# D32_Pro_Benchtop_Test_Board.net
KiCad netlist of a schematic drawn in EAGLE
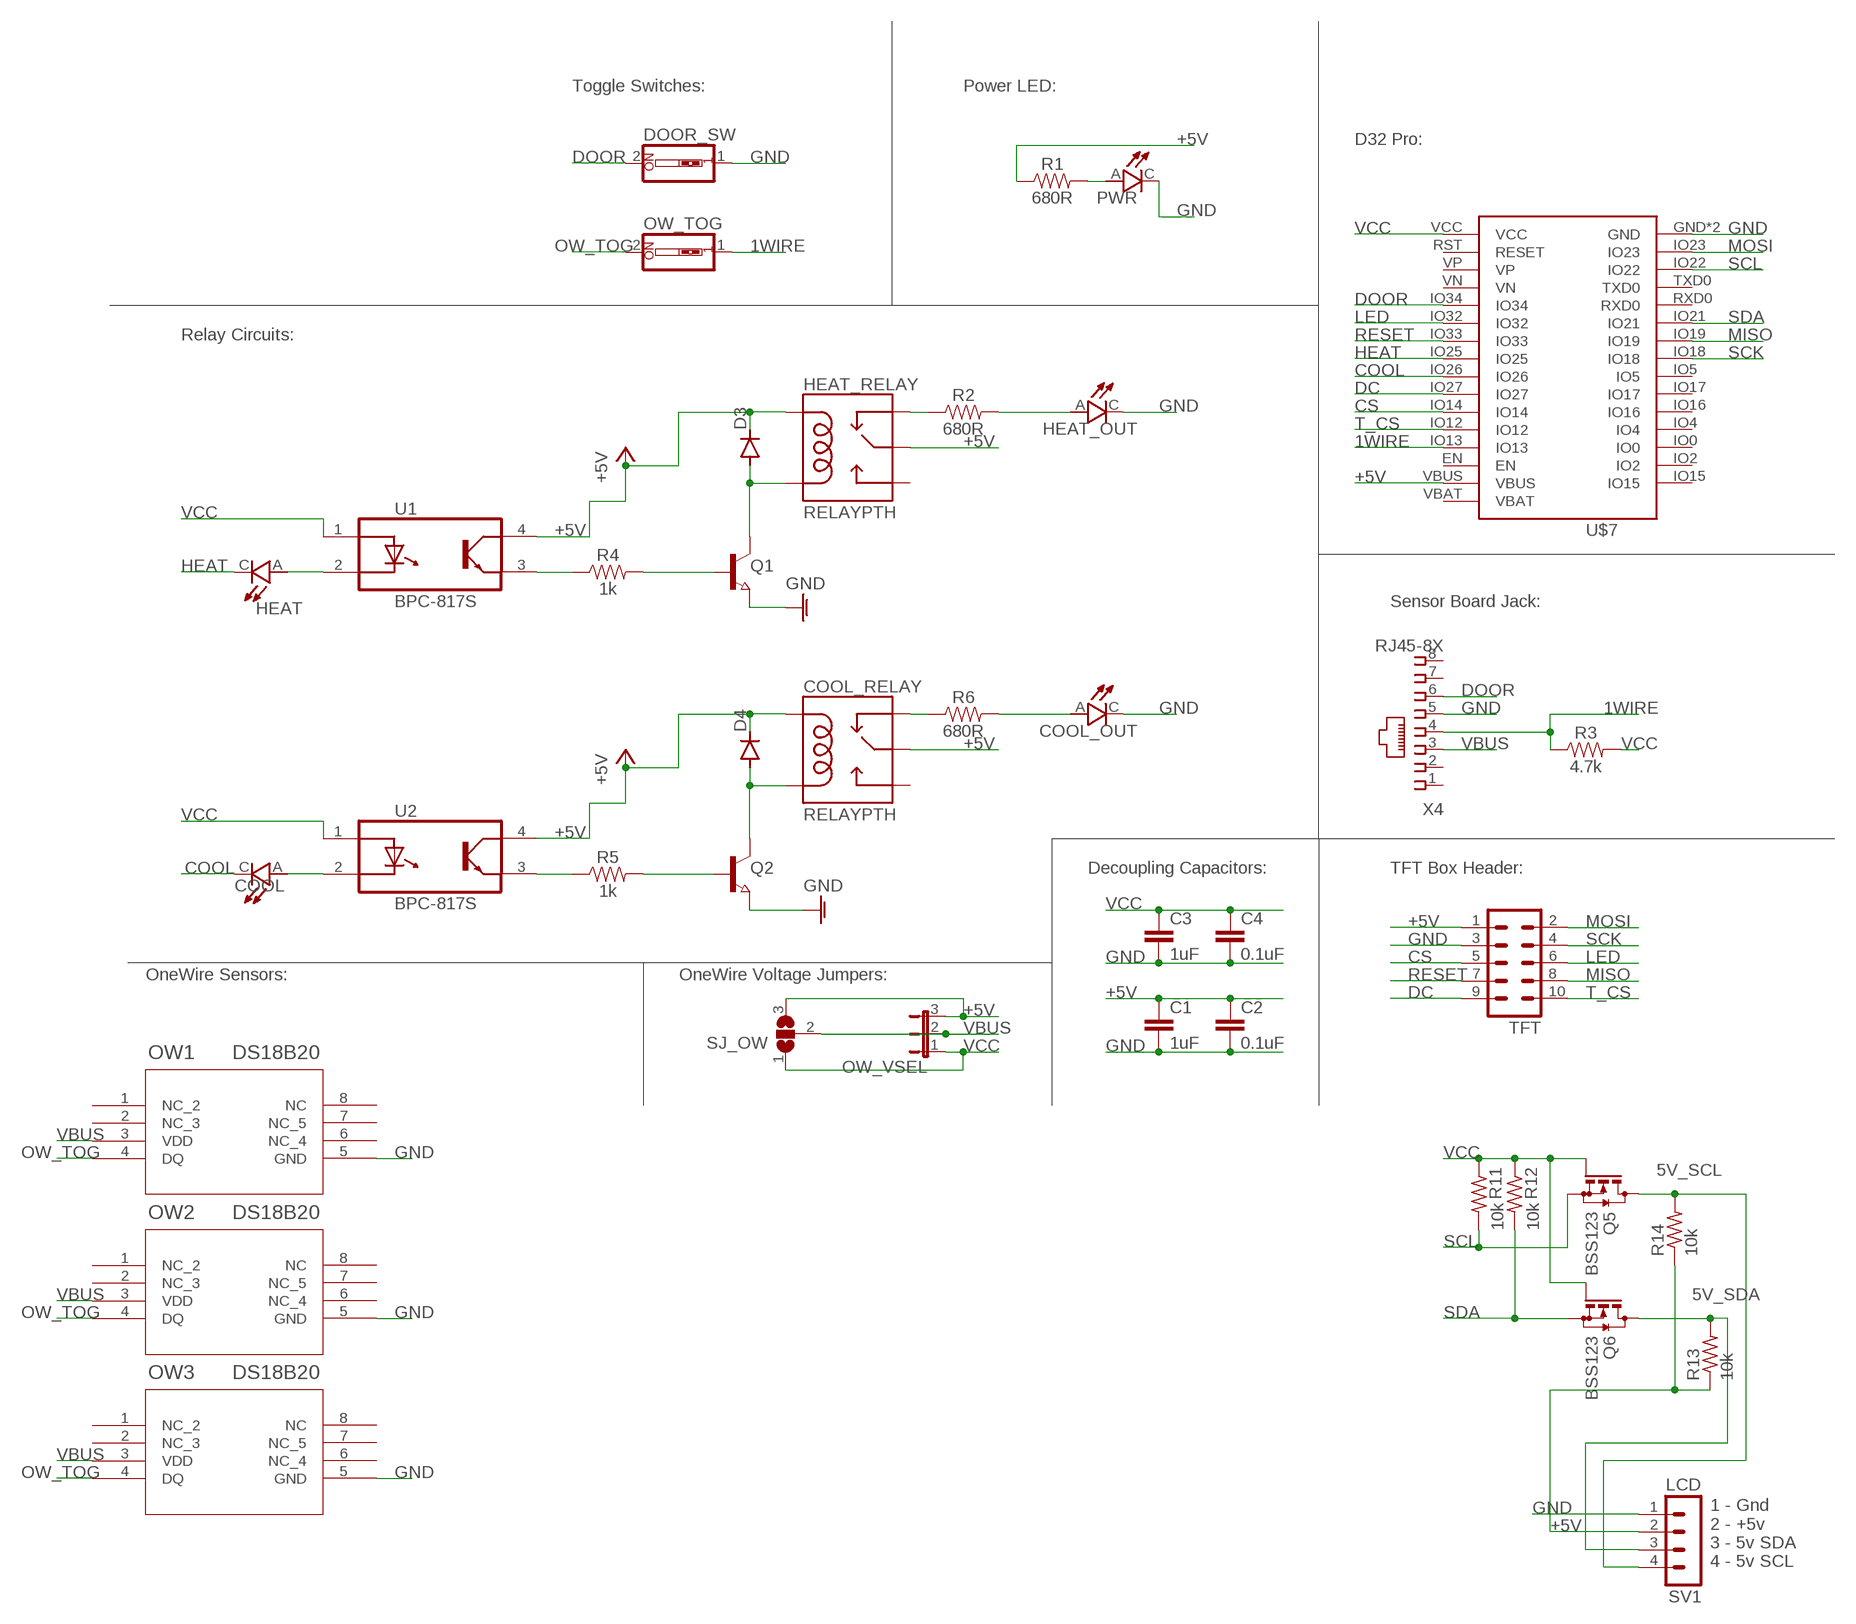
[diagram p0: schematic, sheet 1]

(export (version "E")
  (design (tool "Eeschema 10.0.6"))
  (components
    (comp (ref "C1")
      (value "1uF")
      (footprint "eagle-import:SMD-0805")
      (fields (field (name "LCSC_PART") "C28323"))
      (libsource (lib "eagle-import") (part "CAP_SMD0805"))
    )
    (comp (ref "C2")
      (value "0.1uF")
      (footprint "eagle-import:SMD-0805")
      (fields (field (name "LCSC_PART") "C49678"))
      (libsource (lib "eagle-import") (part "CAP_SMD0805"))
    )
    (comp (ref "C3")
      (value "1uF")
      (footprint "eagle-import:SMD-0805")
      (fields (field (name "LCSC_PART") "C28323"))
      (libsource (lib "eagle-import") (part "CAP_SMD0805"))
    )
    (comp (ref "C4")
      (value "0.1uF")
      (footprint "eagle-import:SMD-0805")
      (fields (field (name "LCSC_PART") "C49678"))
      (libsource (lib "eagle-import") (part "CAP_SMD0805"))
    )
    (comp (ref "COOL")
      (value "LED_0603LED_SMD_0603")
      (footprint "eagle-import:LED_SMD_0603")
      (fields (field (name "LCSC_PART") "C2286") (field (name "LCSC_PART_1") "C2286"))
      (libsource (lib "eagle-import") (part "LED_0603LED_SMD_0603"))
    )
    (comp (ref "COOL_OUT")
      (value "LED_0603LED_SMD_0603")
      (footprint "eagle-import:LED_SMD_0603")
      (fields (field (name "LCSC_PART") "C2286"))
      (libsource (lib "eagle-import") (part "LED_0603LED_SMD_0603"))
    )
    (comp (ref "COOL_RELAY")
      (value "RELAYPTH")
      (footprint "eagle-import:SRD-05VDC-SL-C")
      (fields (field (name "LCSC_PART") "C35449"))
      (libsource (lib "eagle-import") (part "RELAYPTH"))
    )
    (comp (ref "D3")
      (value "DIODE-DO214AC")
      (footprint "eagle-import:DO214AC")
      (fields (field (name "LCSC_PART") "C95872"))
      (libsource (lib "eagle-import") (part "DIODE-DO214AC"))
    )
    (comp (ref "D4")
      (value "DIODE-DO214AC")
      (footprint "eagle-import:DO214AC")
      (fields (field (name "LCSC_PART") "C95872"))
      (libsource (lib "eagle-import") (part "DIODE-DO214AC"))
    )
    (comp (ref "DOOR_SW")
      (value "SW_DIP-1")
      (footprint "eagle-import:EDG-01")
      (fields (field (name "LCSC_PART") "C126888"))
      (libsource (lib "eagle-import") (part "SW_DIP-1"))
    )
    (comp (ref "HEAT")
      (value "LED_0603LED_SMD_0603")
      (footprint "eagle-import:LED_SMD_0603")
      (fields (field (name "LCSC_PART") "C2286") (field (name "LCSC_PART_1") "C2286"))
      (libsource (lib "eagle-import") (part "LED_0603LED_SMD_0603"))
    )
    (comp (ref "HEAT_OUT")
      (value "LED_0603LED_SMD_0603")
      (footprint "eagle-import:LED_SMD_0603")
      (fields (field (name "LCSC_PART") "C2286"))
      (libsource (lib "eagle-import") (part "LED_0603LED_SMD_0603"))
    )
    (comp (ref "HEAT_RELAY")
      (value "RELAYPTH")
      (footprint "eagle-import:SRD-05VDC-SL-C")
      (fields (field (name "LCSC_PART") "C35449"))
      (libsource (lib "eagle-import") (part "RELAYPTH"))
    )
    (comp (ref "OW1")
      (value "DS18B20")
      (footprint "eagle-import:21-0041B_8_MXM")
      (fields
        (field (name "LCSC_PART") "C695837")
        (field (name "MANUFACTURER_PART_NUMBER") "DS18B20Z+T&R")
        (field (name "COPYRIGHT") "Copyright (C) 2024 Ultra Librarian. All rights reserved.")
      )
      (libsource (lib "eagle-import") (part "DS18B20Z+T&R"))
    )
    (comp (ref "OW2")
      (value "DS18B20")
      (footprint "eagle-import:21-0041B_8_MXM")
      (fields
        (field (name "LCSC_PART") "C695837")
        (field (name "MANUFACTURER_PART_NUMBER") "DS18B20Z+T&R")
        (field (name "COPYRIGHT") "Copyright (C) 2024 Ultra Librarian. All rights reserved.")
      )
      (libsource (lib "eagle-import") (part "DS18B20Z+T&R"))
    )
    (comp (ref "OW3")
      (value "DS18B20")
      (footprint "eagle-import:21-0041B_8_MXM")
      (fields
        (field (name "LCSC_PART") "C695837")
        (field (name "MANUFACTURER_PART_NUMBER") "DS18B20Z+T&R")
        (field (name "COPYRIGHT") "Copyright (C) 2024 Ultra Librarian. All rights reserved.")
      )
      (libsource (lib "eagle-import") (part "DS18B20Z+T&R"))
    )
    (comp (ref "OW_TOG")
      (value "SW_DIP-1")
      (footprint "eagle-import:EDG-01")
      (fields (field (name "LCSC_PART") "C126888"))
      (libsource (lib "eagle-import") (part "SW_DIP-1"))
    )
    (comp (ref "OW_VSEL")
      (value "JP2ENOLABEL")
      (footprint "eagle-import:JP2-NOLABEL")
      (fields (field (name "LCSC_PART") "C2937625"))
      (libsource (lib "eagle-import") (part "JP2ENOLABEL"))
    )
    (comp (ref "PWR")
      (value "LED_0603LED_SMD_0603")
      (footprint "eagle-import:LED_SMD_0603")
      (fields (field (name "LCSC_PART") "C2286") (field (name "LCSC_PART_1") "C2286"))
      (libsource (lib "eagle-import") (part "LED_0603LED_SMD_0603"))
    )
    (comp (ref "Q1")
      (value "NPN-TRANSISTOR_SOT23")
      (footprint "eagle-import:SOT23")
      (fields (field (name "LCSC_PART") "C20526"))
      (libsource (lib "eagle-import") (part "NPN-TRANSISTOR_SOT23"))
    )
    (comp (ref "Q2")
      (value "NPN-TRANSISTOR_SOT23")
      (footprint "eagle-import:SOT23")
      (fields (field (name "LCSC_PART") "C20526"))
      (libsource (lib "eagle-import") (part "NPN-TRANSISTOR_SOT23"))
    )
    (comp (ref "Q5")
      (value "BSS123")
      (footprint "eagle-import:SOT23")
      (fields (field (name "LCSC_PART") "C79015"))
      (libsource (lib "eagle-import") (part "BSS123"))
    )
    (comp (ref "Q6")
      (value "BSS123")
      (footprint "eagle-import:SOT23")
      (fields (field (name "LCSC_PART") "C79015"))
      (libsource (lib "eagle-import") (part "BSS123"))
    )
    (comp (ref "R1")
      (value "680R")
      (footprint "eagle-import:SMD-0805")
      (fields (field (name "LCSC_PART") "C17798"))
      (libsource (lib "eagle-import") (part "RES_SMD0805"))
    )
    (comp (ref "R2")
      (value "680R")
      (footprint "eagle-import:SMD-0805")
      (fields (field (name "LCSC_PART") "C17798"))
      (libsource (lib "eagle-import") (part "RES_SMD0805"))
    )
    (comp (ref "R3")
      (value "4.7k")
      (footprint "eagle-import:SMD-0805")
      (fields (field (name "LCSC_PART") "C17673"))
      (libsource (lib "eagle-import") (part "RES_SMD0805"))
    )
    (comp (ref "R4")
      (value "1k")
      (footprint "eagle-import:SMD-0805")
      (fields (field (name "LCSC_PART") "C17513"))
      (libsource (lib "eagle-import") (part "RES_SMD0805"))
    )
    (comp (ref "R5")
      (value "1k")
      (footprint "eagle-import:SMD-0805")
      (fields (field (name "LCSC_PART") "C17513"))
      (libsource (lib "eagle-import") (part "RES_SMD0805"))
    )
    (comp (ref "R6")
      (value "680R")
      (footprint "eagle-import:SMD-0805")
      (fields (field (name "LCSC_PART") "C17798"))
      (libsource (lib "eagle-import") (part "RES_SMD0805"))
    )
    (comp (ref "R11")
      (value "10k")
      (footprint "eagle-import:R0805")
      (fields (field (name "LCSC_PART") "C17902"))
      (libsource (lib "eagle-import") (part "R-US_R0805"))
    )
    (comp (ref "R12")
      (value "10k")
      (footprint "eagle-import:R0805")
      (fields (field (name "LCSC_PART") "C17902"))
      (libsource (lib "eagle-import") (part "R-US_R0805"))
    )
    (comp (ref "R13")
      (value "10k")
      (footprint "eagle-import:R0805")
      (fields (field (name "LCSC_PART") "C17902"))
      (libsource (lib "eagle-import") (part "R-US_R0805"))
    )
    (comp (ref "R14")
      (value "10k")
      (footprint "eagle-import:R0805")
      (fields (field (name "LCSC_PART") "C17902"))
      (libsource (lib "eagle-import") (part "R-US_R0805"))
    )
    (comp (ref "SJ_OW")
      (value "SJ2W")
      (footprint "eagle-import:SJ_2")
      (libsource (lib "eagle-import") (part "SJ2W"))
    )
    (comp (ref "SV1")
      (value "LCD")
      (footprint "eagle-import:HDR-4_VERT")
      (fields (field (name "LCSC_PART") "C2691448"))
      (libsource (lib "eagle-import") (part "HDR-4"))
    )
    (comp (ref "TFT")
      (value "MA05-2")
      (footprint "eagle-import:MA05-2")
      (libsource (lib "eagle-import") (part "MA05-2"))
    )
    (comp (ref "U$7")
      (value "WEMOS-D32D32_PRO_NO-KEEPOUT")
      (footprint "eagle-import:D32_PRO_NO-KEEPOUT")
      (fields (field (name "LCSC_PART") "C18078137"))
      (libsource (lib "eagle-import") (part "WEMOS-D32D32_PRO_NO-KEEPOUT"))
    )
    (comp (ref "U1")
      (value "BPC-817S")
      (footprint "eagle-import:SOIC127P700X210-4N")
      (fields (field (name "LCSC_PART") "C106900"))
      (libsource (lib "eagle-import") (part "BPC-817S"))
    )
    (comp (ref "U2")
      (value "BPC-817S")
      (footprint "eagle-import:SOIC127P700X210-4N")
      (fields (field (name "LCSC_PART") "C106900"))
      (libsource (lib "eagle-import") (part "BPC-817S"))
    )
    (comp (ref "X4")
      (value "RJ45-8X")
      (footprint "eagle-import:RJ45-NO-SHIELD")
      (fields
        (field (name "LCSC_PART") "C3000197")
        (field (name "JLC_Y") "7.55")
        (field (name "LCSC_PART_1") "C3000197")
      )
      (libsource (lib "eagle-import") (part "RJ45-8X"))
    )
  )
  (nets
    (net (code "1") (name "+5V") (class "Default")
      (node (ref "C1") (pin "1") (pinfunction "1_1") (pintype "passive"))
      (node (ref "C2") (pin "1") (pinfunction "1_1") (pintype "passive"))
      (node (ref "COOL_RELAY") (pin "COIL1") (pinfunction "COIL1_COIL1") (pintype "bidirectional"))
      (node (ref "COOL_RELAY") (pin "SWCOMMON") (pinfunction "SWCOMMON_SWCOMMON") (pintype "bidirectional"))
      (node (ref "D3") (pin "C") (pinfunction "C_C") (pintype "passive"))
      (node (ref "D4") (pin "C") (pinfunction "C_C") (pintype "passive"))
      (node (ref "HEAT_RELAY") (pin "COIL1") (pinfunction "COIL1_COIL1") (pintype "bidirectional"))
      (node (ref "HEAT_RELAY") (pin "SWCOMMON") (pinfunction "SWCOMMON_SWCOMMON") (pintype "bidirectional"))
      (node (ref "OW_VSEL") (pin "3") (pinfunction "3_3") (pintype "passive"))
      (node (ref "R1") (pin "1") (pinfunction "1_1") (pintype "passive"))
      (node (ref "R13") (pin "1") (pinfunction "1_1") (pintype "passive"))
      (node (ref "R14") (pin "1") (pinfunction "1_1") (pintype "passive"))
      (node (ref "SJ_OW") (pin "3") (pinfunction "3_3") (pintype "passive"))
      (node (ref "SV1") (pin "2") (pinfunction "2_2") (pintype "passive"))
      (node (ref "TFT") (pin "1") (pinfunction "1_1") (pintype "passive"))
      (node (ref "U$7") (pin "VBUS") (pinfunction "VBUS_VBUS") (pintype "bidirectional"))
      (node (ref "U1") (pin "4") (pinfunction "CO_4") (pintype "passive"))
      (node (ref "U2") (pin "4") (pinfunction "CO_4") (pintype "passive"))
    )
    (net (code "2") (name "/1WIRE") (class "Default")
      (node (ref "OW_TOG") (pin "1") (pinfunction "1_1") (pintype "passive"))
      (node (ref "R3") (pin "1") (pinfunction "1_1") (pintype "passive"))
      (node (ref "U$7") (pin "IO13") (pinfunction "IO13_IO13") (pintype "bidirectional"))
      (node (ref "X4") (pin "4") (pinfunction "4_4") (pintype "passive"))
    )
    (net (code "3") (name "/5V_SCL") (class "Default")
      (node (ref "Q5") (pin "3") (pinfunction "D_3") (pintype "passive"))
      (node (ref "R14") (pin "2") (pinfunction "2_2") (pintype "passive"))
      (node (ref "SV1") (pin "4") (pinfunction "4_4") (pintype "passive"))
    )
    (net (code "4") (name "/5V_SDA") (class "Default")
      (node (ref "Q6") (pin "3") (pinfunction "D_3") (pintype "passive"))
      (node (ref "R13") (pin "2") (pinfunction "2_2") (pintype "passive"))
      (node (ref "SV1") (pin "3") (pinfunction "3_3") (pintype "passive"))
    )
    (net (code "5") (name "/COOL") (class "Default")
      (node (ref "COOL") (pin "C") (pinfunction "C_C") (pintype "passive"))
      (node (ref "U$7") (pin "IO26") (pinfunction "IO26_IO26") (pintype "bidirectional"))
    )
    (net (code "6") (name "/CS") (class "Default")
      (node (ref "TFT") (pin "5") (pinfunction "5_5") (pintype "passive"))
      (node (ref "U$7") (pin "IO14") (pinfunction "IO14_IO14") (pintype "bidirectional"))
    )
    (net (code "7") (name "/DC") (class "Default")
      (node (ref "TFT") (pin "9") (pinfunction "9_9") (pintype "passive"))
      (node (ref "U$7") (pin "IO27") (pinfunction "IO27_IO27") (pintype "bidirectional"))
    )
    (net (code "8") (name "/DOOR") (class "Default")
      (node (ref "DOOR_SW") (pin "2") (pinfunction "2_2") (pintype "passive"))
      (node (ref "U$7") (pin "IO34") (pinfunction "IO34_IO34") (pintype "bidirectional"))
      (node (ref "X4") (pin "6") (pinfunction "6_6") (pintype "passive"))
    )
    (net (code "9") (name "/HEAT") (class "Default")
      (node (ref "HEAT") (pin "C") (pinfunction "C_C") (pintype "passive"))
      (node (ref "U$7") (pin "IO25") (pinfunction "IO25_IO25") (pintype "bidirectional"))
    )
    (net (code "10") (name "/LED") (class "Default")
      (node (ref "TFT") (pin "6") (pinfunction "6_6") (pintype "passive"))
      (node (ref "U$7") (pin "IO32") (pinfunction "IO32_IO32") (pintype "bidirectional"))
    )
    (net (code "11") (name "/MISO") (class "Default")
      (node (ref "TFT") (pin "8") (pinfunction "8_8") (pintype "passive"))
      (node (ref "U$7") (pin "IO19") (pinfunction "IO19_IO19") (pintype "bidirectional"))
    )
    (net (code "12") (name "/MOSI") (class "Default")
      (node (ref "TFT") (pin "2") (pinfunction "2_2") (pintype "passive"))
      (node (ref "U$7") (pin "IO23") (pinfunction "IO23_IO23") (pintype "bidirectional"))
    )
    (net (code "13") (name "/OW_TOG") (class "Default")
      (node (ref "OW1") (pin "4") (pinfunction "DQ_4") (pintype "bidirectional"))
      (node (ref "OW2") (pin "4") (pinfunction "DQ_4") (pintype "bidirectional"))
      (node (ref "OW3") (pin "4") (pinfunction "DQ_4") (pintype "bidirectional"))
      (node (ref "OW_TOG") (pin "2") (pinfunction "2_2") (pintype "passive"))
    )
    (net (code "14") (name "/RESET") (class "Default")
      (node (ref "TFT") (pin "7") (pinfunction "7_7") (pintype "passive"))
      (node (ref "U$7") (pin "IO33") (pinfunction "IO33_IO33") (pintype "bidirectional"))
    )
    (net (code "15") (name "/SCK") (class "Default")
      (node (ref "TFT") (pin "4") (pinfunction "4_4") (pintype "passive"))
      (node (ref "U$7") (pin "IO18") (pinfunction "IO18_IO18") (pintype "bidirectional"))
    )
    (net (code "16") (name "/SCL") (class "Default")
      (node (ref "Q5") (pin "2") (pinfunction "S_2") (pintype "passive"))
      (node (ref "R11") (pin "2") (pinfunction "2_2") (pintype "passive"))
      (node (ref "U$7") (pin "IO22") (pinfunction "IO22_IO22") (pintype "bidirectional"))
    )
    (net (code "17") (name "/SDA") (class "Default")
      (node (ref "Q6") (pin "2") (pinfunction "S_2") (pintype "passive"))
      (node (ref "R12") (pin "2") (pinfunction "2_2") (pintype "passive"))
      (node (ref "U$7") (pin "IO21") (pinfunction "IO21_IO21") (pintype "bidirectional"))
    )
    (net (code "18") (name "/T_CS") (class "Default")
      (node (ref "TFT") (pin "10") (pinfunction "10_10") (pintype "passive"))
      (node (ref "U$7") (pin "IO12") (pinfunction "IO12_IO12") (pintype "bidirectional"))
    )
    (net (code "19") (name "/VBUS") (class "Default")
      (node (ref "OW1") (pin "3") (pinfunction "VDD_3") (pintype "power_in"))
      (node (ref "OW2") (pin "3") (pinfunction "VDD_3") (pintype "power_in"))
      (node (ref "OW3") (pin "3") (pinfunction "VDD_3") (pintype "power_in"))
      (node (ref "OW_VSEL") (pin "2") (pinfunction "2_2") (pintype "passive"))
      (node (ref "SJ_OW") (pin "2") (pinfunction "2_2") (pintype "passive"))
      (node (ref "X4") (pin "3") (pinfunction "3_3") (pintype "passive"))
    )
    (net (code "20") (name "/VCC") (class "Default")
      (node (ref "C3") (pin "1") (pinfunction "1_1") (pintype "passive"))
      (node (ref "C4") (pin "1") (pinfunction "1_1") (pintype "passive"))
      (node (ref "OW_VSEL") (pin "1") (pinfunction "1_1") (pintype "passive"))
      (node (ref "Q5") (pin "1") (pinfunction "G_1") (pintype "passive"))
      (node (ref "Q6") (pin "1") (pinfunction "G_1") (pintype "passive"))
      (node (ref "R11") (pin "1") (pinfunction "1_1") (pintype "passive"))
      (node (ref "R12") (pin "1") (pinfunction "1_1") (pintype "passive"))
      (node (ref "R3") (pin "2") (pinfunction "2_2") (pintype "passive"))
      (node (ref "SJ_OW") (pin "1") (pinfunction "1_1") (pintype "passive"))
      (node (ref "U$7") (pin "VCC") (pinfunction "VCC_VCC") (pintype "power_in"))
      (node (ref "U1") (pin "1") (pinfunction "A_1") (pintype "passive"))
      (node (ref "U2") (pin "1") (pinfunction "A_1") (pintype "passive"))
    )
    (net (code "21") (name "GNDA") (class "Default")
      (node (ref "C1") (pin "2") (pinfunction "2_2") (pintype "passive"))
      (node (ref "C2") (pin "2") (pinfunction "2_2") (pintype "passive"))
      (node (ref "C3") (pin "2") (pinfunction "2_2") (pintype "passive"))
      (node (ref "C4") (pin "2") (pinfunction "2_2") (pintype "passive"))
      (node (ref "COOL_OUT") (pin "C") (pinfunction "C_C") (pintype "passive"))
      (node (ref "DOOR_SW") (pin "1") (pinfunction "1_1") (pintype "passive"))
      (node (ref "HEAT_OUT") (pin "C") (pinfunction "C_C") (pintype "passive"))
      (node (ref "OW1") (pin "5") (pinfunction "GND_5") (pintype "power_in"))
      (node (ref "OW2") (pin "5") (pinfunction "GND_5") (pintype "power_in"))
      (node (ref "OW3") (pin "5") (pinfunction "GND_5") (pintype "power_in"))
      (node (ref "PWR") (pin "C") (pinfunction "C_C") (pintype "passive"))
      (node (ref "Q1") (pin "2") (pinfunction "E_2") (pintype "passive"))
      (node (ref "Q2") (pin "2") (pinfunction "E_2") (pintype "passive"))
      (node (ref "SV1") (pin "1") (pinfunction "1_1") (pintype "passive"))
      (node (ref "TFT") (pin "3") (pinfunction "3_3") (pintype "passive"))
      (node (ref "U$7") (pin "GND") (pinfunction "GND_GND") (pintype "power_in"))
      (node (ref "U$7") (pin "GND2") (pinfunction "GND_GND2") (pintype "power_in"))
      (node (ref "X4") (pin "5") (pinfunction "5_5") (pintype "passive"))
    )
    (net (code "22") (name "Net-(COOL_OUT-PadA)") (class "Default")
      (node (ref "COOL_OUT") (pin "A") (pinfunction "A_A") (pintype "passive"))
      (node (ref "R6") (pin "2") (pinfunction "2_2") (pintype "passive"))
    )
    (net (code "23") (name "Net-(COOL_RELAY-SWCLOSE)") (class "Default")
      (node (ref "COOL_RELAY") (pin "SWCLOSED") (pinfunction "SWCLOSE_SWCLOSED") (pintype "bidirectional"))
      (node (ref "R6") (pin "1") (pinfunction "1_1") (pintype "passive"))
    )
    (net (code "24") (name "Net-(HEAT_OUT-PadA)") (class "Default")
      (node (ref "HEAT_OUT") (pin "A") (pinfunction "A_A") (pintype "passive"))
      (node (ref "R2") (pin "2") (pinfunction "2_2") (pintype "passive"))
    )
    (net (code "25") (name "Net-(HEAT_RELAY-SWCLOSE)") (class "Default")
      (node (ref "HEAT_RELAY") (pin "SWCLOSED") (pinfunction "SWCLOSE_SWCLOSED") (pintype "bidirectional"))
      (node (ref "R2") (pin "1") (pinfunction "1_1") (pintype "passive"))
    )
    (net (code "26") (name "Net-(PWR-PadA)") (class "Default")
      (node (ref "PWR") (pin "A") (pinfunction "A_A") (pintype "passive"))
      (node (ref "R1") (pin "2") (pinfunction "2_2") (pintype "passive"))
    )
    (net (code "27") (name "Net-(Q1-B)") (class "Default")
      (node (ref "Q1") (pin "1") (pinfunction "B_1") (pintype "passive"))
      (node (ref "R4") (pin "2") (pinfunction "2_2") (pintype "passive"))
    )
    (net (code "28") (name "Net-(Q1-C)") (class "Default")
      (node (ref "D3") (pin "A") (pinfunction "A_A") (pintype "passive"))
      (node (ref "HEAT_RELAY") (pin "COIL0") (pinfunction "COIL0_COIL0") (pintype "bidirectional"))
      (node (ref "Q1") (pin "3") (pinfunction "C_3") (pintype "passive"))
    )
    (net (code "29") (name "Net-(Q2-B)") (class "Default")
      (node (ref "Q2") (pin "1") (pinfunction "B_1") (pintype "passive"))
      (node (ref "R5") (pin "2") (pinfunction "2_2") (pintype "passive"))
    )
    (net (code "30") (name "Net-(Q2-C)") (class "Default")
      (node (ref "COOL_RELAY") (pin "COIL0") (pinfunction "COIL0_COIL0") (pintype "bidirectional"))
      (node (ref "D4") (pin "A") (pinfunction "A_A") (pintype "passive"))
      (node (ref "Q2") (pin "3") (pinfunction "C_3") (pintype "passive"))
    )
    (net (code "31") (name "Net-(U1-C)") (class "Default")
      (node (ref "HEAT") (pin "A") (pinfunction "A_A") (pintype "passive"))
      (node (ref "U1") (pin "2") (pinfunction "C_2") (pintype "passive"))
    )
    (net (code "32") (name "Net-(U1-E)") (class "Default")
      (node (ref "R4") (pin "1") (pinfunction "1_1") (pintype "passive"))
      (node (ref "U1") (pin "3") (pinfunction "E_3") (pintype "passive"))
    )
    (net (code "33") (name "Net-(U2-C)") (class "Default")
      (node (ref "COOL") (pin "A") (pinfunction "A_A") (pintype "passive"))
      (node (ref "U2") (pin "2") (pinfunction "C_2") (pintype "passive"))
    )
    (net (code "34") (name "Net-(U2-E)") (class "Default")
      (node (ref "R5") (pin "1") (pinfunction "1_1") (pintype "passive"))
      (node (ref "U2") (pin "3") (pinfunction "E_3") (pintype "passive"))
    )
    (net (code "35") (name "unconnected-(COOL_RELAY-PadSWOPEN)") (class "Default")
      (node (ref "COOL_RELAY") (pin "SWOPEN") (pinfunction "SWOPEN_SWOPEN") (pintype "bidirectional"))
    )
    (net (code "36") (name "unconnected-(HEAT_RELAY-PadSWOPEN)") (class "Default")
      (node (ref "HEAT_RELAY") (pin "SWOPEN") (pinfunction "SWOPEN_SWOPEN") (pintype "bidirectional"))
    )
    (net (code "37") (name "unconnected-(OW1-NC-Pad8)") (class "Default")
      (node (ref "OW1") (pin "8") (pinfunction "NC_8") (pintype "no_connect"))
    )
    (net (code "38") (name "unconnected-(OW1-NC_2-Pad1)") (class "Default")
      (node (ref "OW1") (pin "1") (pinfunction "NC_2_1") (pintype "no_connect"))
    )
    (net (code "39") (name "unconnected-(OW1-NC_3-Pad2)") (class "Default")
      (node (ref "OW1") (pin "2") (pinfunction "NC_3_2") (pintype "no_connect"))
    )
    (net (code "40") (name "unconnected-(OW1-NC_4-Pad6)") (class "Default")
      (node (ref "OW1") (pin "6") (pinfunction "NC_4_6") (pintype "no_connect"))
    )
    (net (code "41") (name "unconnected-(OW1-NC_5-Pad7)") (class "Default")
      (node (ref "OW1") (pin "7") (pinfunction "NC_5_7") (pintype "no_connect"))
    )
    (net (code "42") (name "unconnected-(OW2-NC-Pad8)") (class "Default")
      (node (ref "OW2") (pin "8") (pinfunction "NC_8") (pintype "no_connect"))
    )
    (net (code "43") (name "unconnected-(OW2-NC_2-Pad1)") (class "Default")
      (node (ref "OW2") (pin "1") (pinfunction "NC_2_1") (pintype "no_connect"))
    )
    (net (code "44") (name "unconnected-(OW2-NC_3-Pad2)") (class "Default")
      (node (ref "OW2") (pin "2") (pinfunction "NC_3_2") (pintype "no_connect"))
    )
    (net (code "45") (name "unconnected-(OW2-NC_4-Pad6)") (class "Default")
      (node (ref "OW2") (pin "6") (pinfunction "NC_4_6") (pintype "no_connect"))
    )
    (net (code "46") (name "unconnected-(OW2-NC_5-Pad7)") (class "Default")
      (node (ref "OW2") (pin "7") (pinfunction "NC_5_7") (pintype "no_connect"))
    )
    (net (code "47") (name "unconnected-(OW3-NC-Pad8)") (class "Default")
      (node (ref "OW3") (pin "8") (pinfunction "NC_8") (pintype "no_connect"))
    )
    (net (code "48") (name "unconnected-(OW3-NC_2-Pad1)") (class "Default")
      (node (ref "OW3") (pin "1") (pinfunction "NC_2_1") (pintype "no_connect"))
    )
    (net (code "49") (name "unconnected-(OW3-NC_3-Pad2)") (class "Default")
      (node (ref "OW3") (pin "2") (pinfunction "NC_3_2") (pintype "no_connect"))
    )
    (net (code "50") (name "unconnected-(OW3-NC_4-Pad6)") (class "Default")
      (node (ref "OW3") (pin "6") (pinfunction "NC_4_6") (pintype "no_connect"))
    )
    (net (code "51") (name "unconnected-(OW3-NC_5-Pad7)") (class "Default")
      (node (ref "OW3") (pin "7") (pinfunction "NC_5_7") (pintype "no_connect"))
    )
    (net (code "52") (name "unconnected-(U$7-PadEN)") (class "Default")
      (node (ref "U$7") (pin "EN") (pinfunction "EN_EN") (pintype "bidirectional"))
    )
    (net (code "53") (name "unconnected-(U$7-PadIO0)") (class "Default")
      (node (ref "U$7") (pin "IO0") (pinfunction "IO0_IO0") (pintype "bidirectional"))
    )
    (net (code "54") (name "unconnected-(U$7-PadIO2)") (class "Default")
      (node (ref "U$7") (pin "IO2") (pinfunction "IO2_IO2") (pintype "bidirectional"))
    )
    (net (code "55") (name "unconnected-(U$7-PadIO4)") (class "Default")
      (node (ref "U$7") (pin "IO4") (pinfunction "IO4_IO4") (pintype "bidirectional"))
    )
    (net (code "56") (name "unconnected-(U$7-PadIO5)") (class "Default")
      (node (ref "U$7") (pin "IO5") (pinfunction "IO5_IO5") (pintype "bidirectional"))
    )
    (net (code "57") (name "unconnected-(U$7-PadIO15)") (class "Default")
      (node (ref "U$7") (pin "IO15") (pinfunction "IO15_IO15") (pintype "bidirectional"))
    )
    (net (code "58") (name "unconnected-(U$7-PadIO16)") (class "Default")
      (node (ref "U$7") (pin "IO16") (pinfunction "IO16_IO16") (pintype "bidirectional"))
    )
    (net (code "59") (name "unconnected-(U$7-PadIO17)") (class "Default")
      (node (ref "U$7") (pin "IO17") (pinfunction "IO17_IO17") (pintype "bidirectional"))
    )
    (net (code "60") (name "unconnected-(U$7-PadRXD0)") (class "Default")
      (node (ref "U$7") (pin "RXD0") (pinfunction "RXD0_RXD0") (pintype "input"))
    )
    (net (code "61") (name "unconnected-(U$7-PadTXD0)") (class "Default")
      (node (ref "U$7") (pin "TXD0") (pinfunction "TXD0_TXD0") (pintype "output"))
    )
    (net (code "62") (name "unconnected-(U$7-PadVBAT)") (class "Default")
      (node (ref "U$7") (pin "VBAT") (pinfunction "VBAT_VBAT") (pintype "bidirectional"))
    )
    (net (code "63") (name "unconnected-(U$7-PadVN)") (class "Default")
      (node (ref "U$7") (pin "VN") (pinfunction "VN_VN") (pintype "bidirectional"))
    )
    (net (code "64") (name "unconnected-(U$7-PadVP)") (class "Default")
      (node (ref "U$7") (pin "VP") (pinfunction "VP_VP") (pintype "bidirectional"))
    )
    (net (code "65") (name "unconnected-(U$7-RESET-PadRST)") (class "Default")
      (node (ref "U$7") (pin "RST") (pinfunction "RESET_RST") (pintype "bidirectional"))
    )
    (net (code "66") (name "unconnected-(X4-Pad1)") (class "Default")
      (node (ref "X4") (pin "1") (pinfunction "1_1") (pintype "passive"))
    )
    (net (code "67") (name "unconnected-(X4-Pad2)") (class "Default")
      (node (ref "X4") (pin "2") (pinfunction "2_2") (pintype "passive"))
    )
    (net (code "68") (name "unconnected-(X4-Pad7)") (class "Default")
      (node (ref "X4") (pin "7") (pinfunction "7_7") (pintype "passive"))
    )
    (net (code "69") (name "unconnected-(X4-Pad8)") (class "Default")
      (node (ref "X4") (pin "8") (pinfunction "8_8") (pintype "passive"))
    )
  )
)
